# line_kick.net
KiCad netlist of a schematic drawn in EAGLE
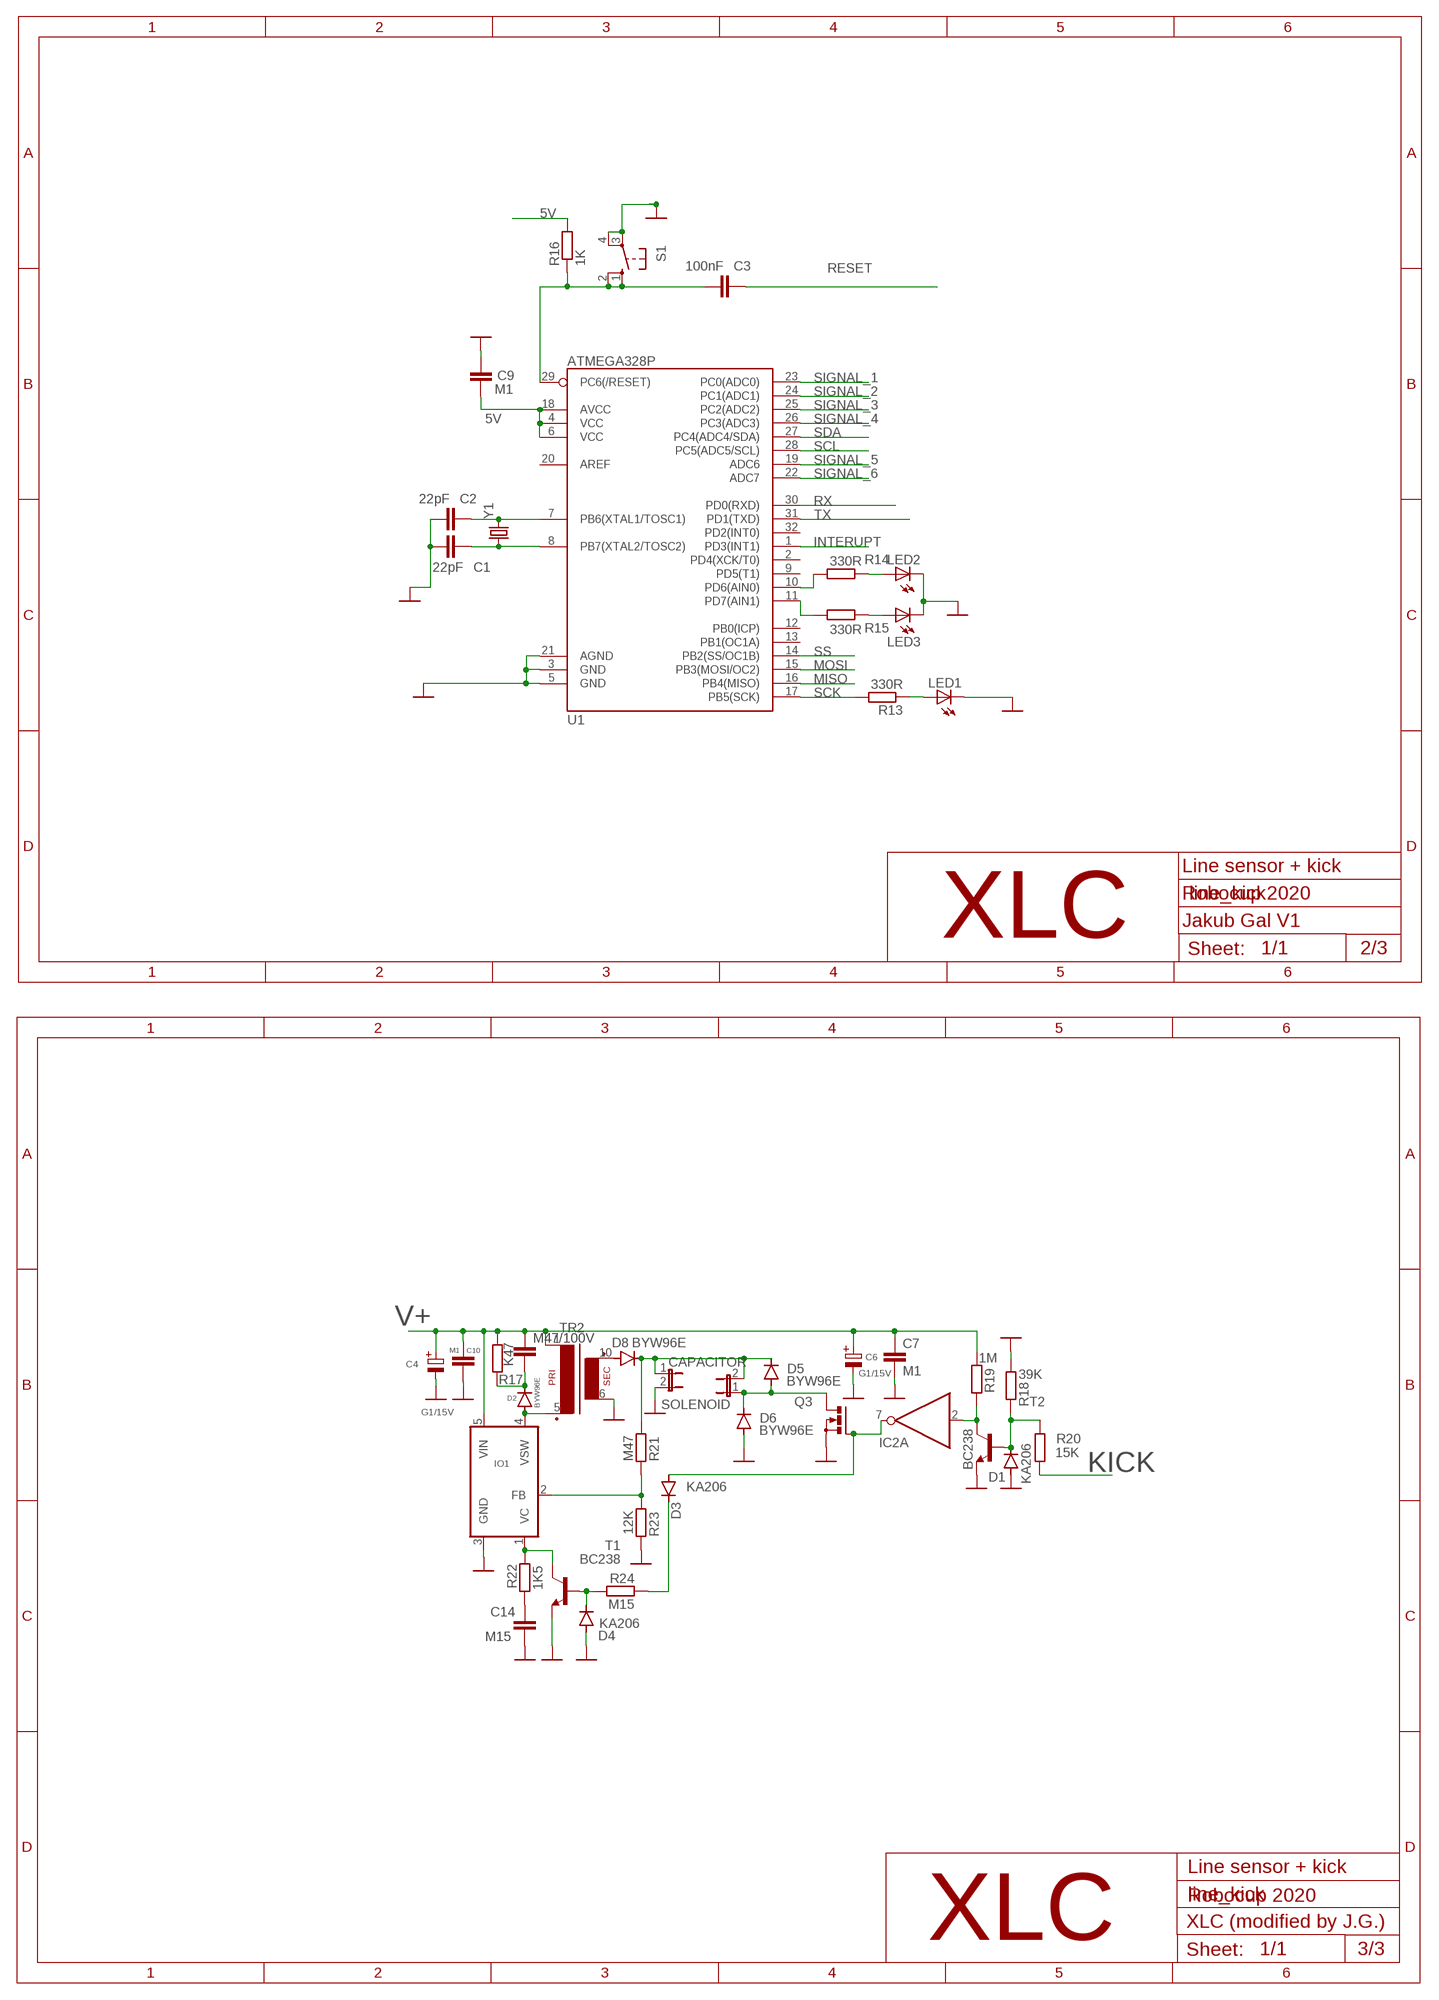
[diagram p0: schematic, sheet 1, part 1 of 2]
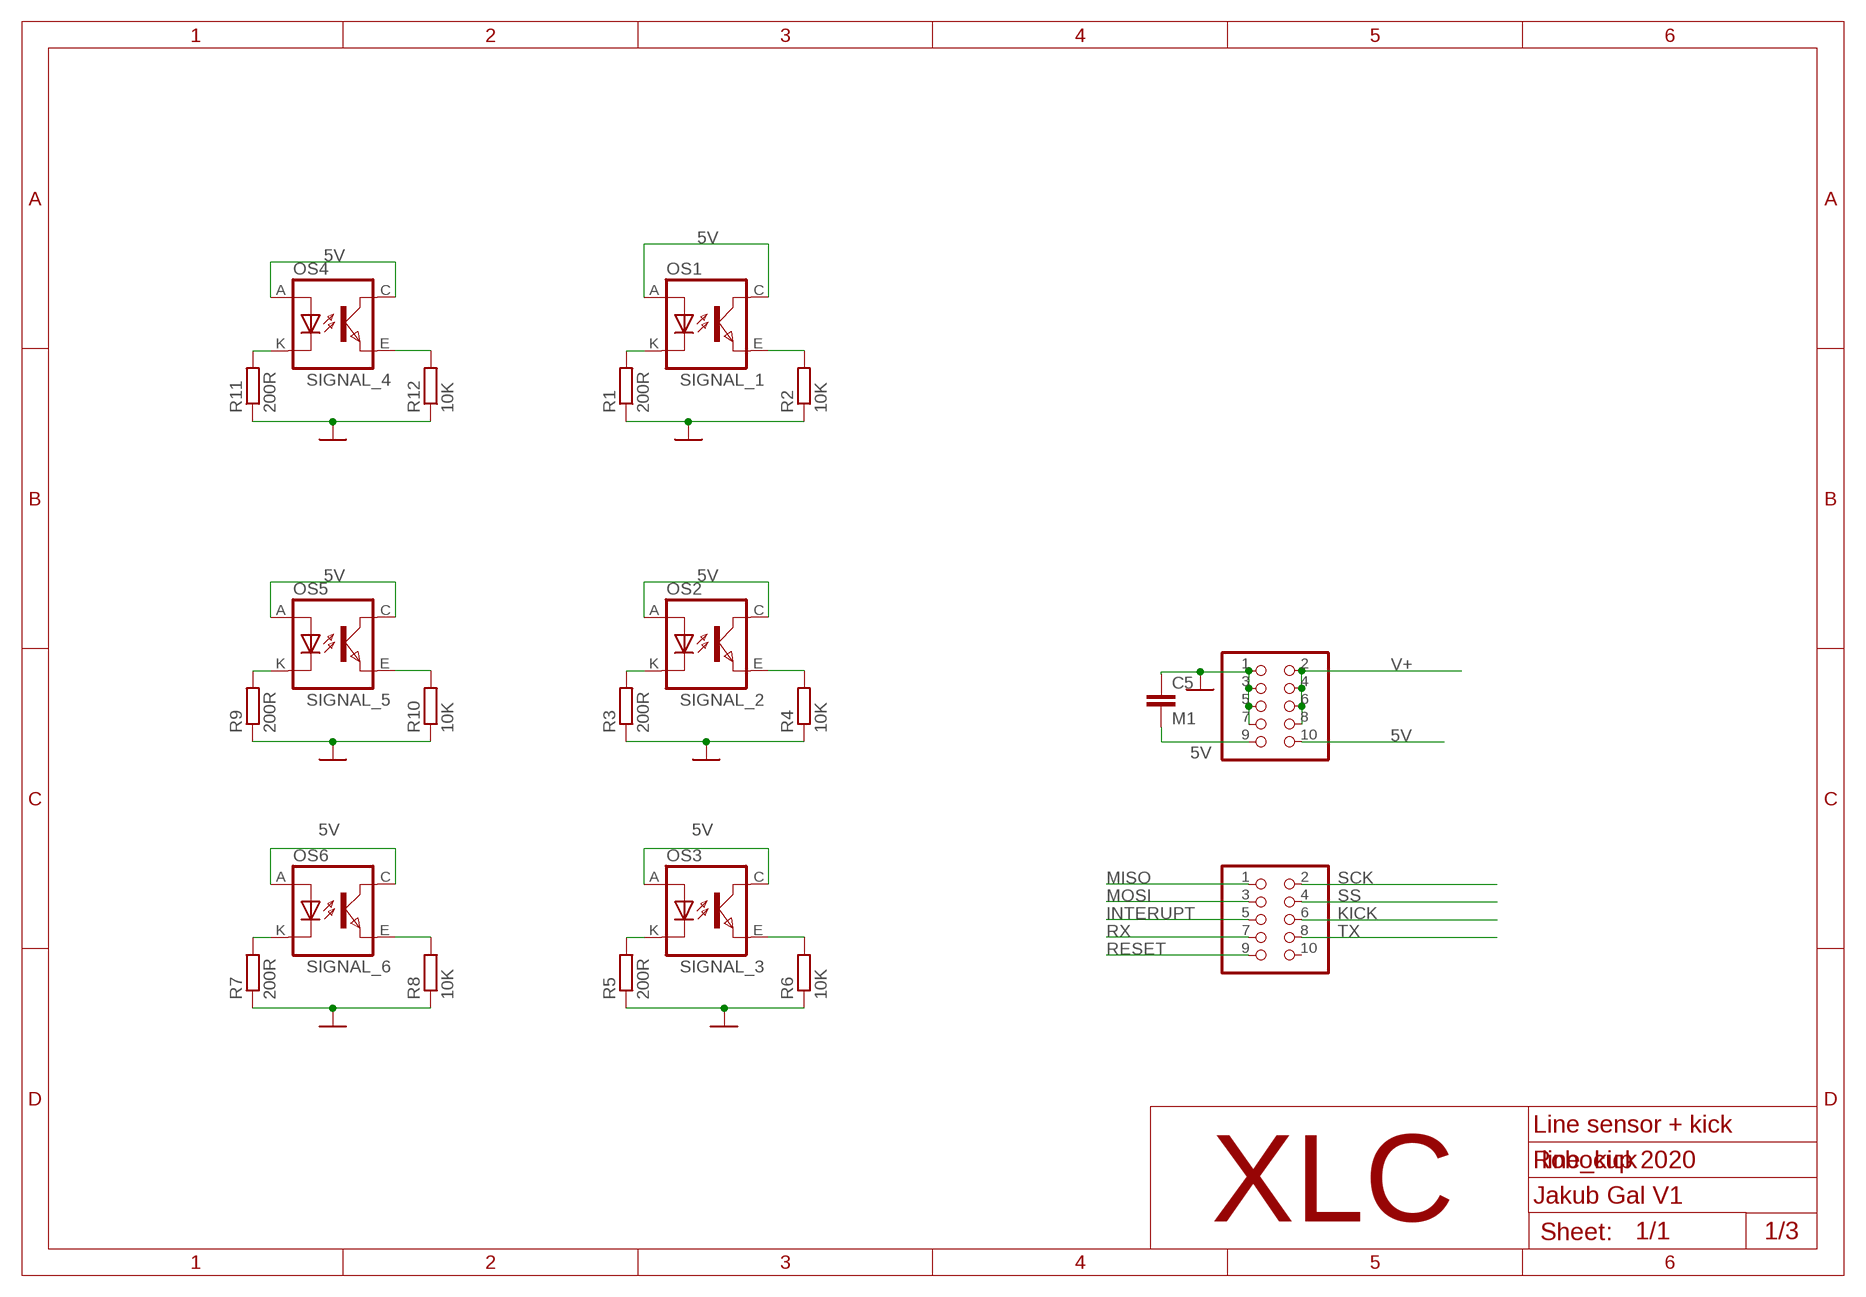
[diagram p1: schematic, sheet 1, part 2 of 2]

(export (version "E")
  (design (tool "Eeschema 10.0.6"))
  (components
    (comp (ref "C1")
      (value "22pF")
      (footprint "eagle-import:C0603")
      (libsource (lib "eagle-import") (part "C-EUC0603"))
    )
    (comp (ref "C2")
      (value "22pF")
      (footprint "eagle-import:C0603")
      (libsource (lib "eagle-import") (part "C-EUC0603"))
    )
    (comp (ref "C3")
      (value "100nF")
      (footprint "eagle-import:C0603")
      (libsource (lib "eagle-import") (part "C-EUC0603"))
    )
    (comp (ref "C4")
      (value "G1/15V")
      (footprint "eagle-import:E-2,5_7-RAD")
      (libsource (lib "eagle-import") (part "KOND-ELEKT-2,5/7"))
    )
    (comp (ref "C5")
      (value "M1")
      (footprint "eagle-import:C0603")
      (libsource (lib "eagle-import") (part "rcl_334_C-EUC0603"))
    )
    (comp (ref "C6")
      (value "G1/15V")
      (footprint "eagle-import:E-2,5_7-RAD")
      (libsource (lib "eagle-import") (part "KOND-ELEKT-2,5/7"))
    )
    (comp (ref "C7")
      (value "M1")
      (footprint "eagle-import:C0805K")
      (libsource (lib "eagle-import") (part "resistor_348_C-EUC0805K"))
    )
    (comp (ref "C9")
      (value "M1")
      (footprint "eagle-import:C0603")
      (libsource (lib "eagle-import") (part "C-EUC0603"))
    )
    (comp (ref "C10")
      (value "M1")
      (footprint "eagle-import:C0805K")
      (libsource (lib "eagle-import") (part "resistor_348_C-EUC0805K"))
    )
    (comp (ref "C14")
      (value "M15")
      (footprint "eagle-import:C0805K")
      (libsource (lib "eagle-import") (part "resistor_348_C-EUC0805K"))
    )
    (comp (ref "CAPACITOR")
      (value "JP1E")
      (footprint "eagle-import:JP1")
      (libsource (lib "eagle-import") (part "JP1E"))
    )
    (comp (ref "D1")
      (value "KA206")
      (footprint "eagle-import:D-7.5")
      (libsource (lib "eagle-import") (part "DIODE-D-7.5"))
    )
    (comp (ref "D2")
      (value "BYW96E")
      (footprint "eagle-import:SOD64-10")
      (libsource (lib "eagle-import") (part "BYW96"))
    )
    (comp (ref "D3")
      (value "KA206")
      (footprint "eagle-import:D-7.5")
      (libsource (lib "eagle-import") (part "DIODE-D-7.5"))
    )
    (comp (ref "D4")
      (value "KA206")
      (footprint "eagle-import:D-7.5")
      (libsource (lib "eagle-import") (part "DIODE-D-7.5"))
    )
    (comp (ref "D5")
      (value "BYW96E")
      (footprint "eagle-import:SOD64-10")
      (libsource (lib "eagle-import") (part "BYW96"))
    )
    (comp (ref "D6")
      (value "BYW96E")
      (footprint "eagle-import:SOD64-10")
      (libsource (lib "eagle-import") (part "BYW96"))
    )
    (comp (ref "D8")
      (value "BYW96E")
      (footprint "eagle-import:SOD64-10")
      (libsource (lib "eagle-import") (part "BYW96"))
    )
    (comp (ref "IC2")
      (value "MIC4423BM")
      (footprint "eagle-import:SO08")
      (libsource (lib "eagle-import") (part "MIC4423BM"))
    )
    (comp (ref "IO1")
      (value "LT1071V")
      (footprint "eagle-import:TO220-5P")
      (libsource (lib "eagle-import") (part "LT1071V"))
    )
    (comp (ref "JP2")
      (value "PINHD-2X5")
      (footprint "eagle-import:2X05")
      (libsource (lib "eagle-import") (part "PINHD-2X5"))
    )
    (comp (ref "JP3")
      (value "PINHD-2X5")
      (footprint "eagle-import:2X05")
      (libsource (lib "eagle-import") (part "PINHD-2X5"))
    )
    (comp (ref "LED1")
      (value "LEDCHIPLED_0603")
      (footprint "eagle-import:CHIPLED_0603")
      (libsource (lib "eagle-import") (part "LEDCHIPLED_0603"))
    )
    (comp (ref "LED2")
      (value "LEDCHIPLED_0603")
      (footprint "eagle-import:CHIPLED_0603")
      (libsource (lib "eagle-import") (part "LEDCHIPLED_0603"))
    )
    (comp (ref "LED3")
      (value "LEDCHIPLED_0603")
      (footprint "eagle-import:CHIPLED_0603")
      (libsource (lib "eagle-import") (part "LEDCHIPLED_0603"))
    )
    (comp (ref "M47/100V")
      (value "C-EUC0805K")
      (footprint "eagle-import:C0805K")
      (libsource (lib "eagle-import") (part "resistor_348_C-EUC0805K"))
    )
    (comp (ref "OS1")
      (value "TCRT5000")
      (footprint "eagle-import:TCRT5000")
      (libsource (lib "eagle-import") (part "TCRT5000"))
    )
    (comp (ref "OS2")
      (value "TCRT5000")
      (footprint "eagle-import:TCRT5000")
      (libsource (lib "eagle-import") (part "TCRT5000"))
    )
    (comp (ref "OS3")
      (value "TCRT5000")
      (footprint "eagle-import:TCRT5000")
      (libsource (lib "eagle-import") (part "TCRT5000"))
    )
    (comp (ref "OS4")
      (value "TCRT5000")
      (footprint "eagle-import:TCRT5000")
      (fields (field (name "SPICEPREFIX") "O"))
      (libsource (lib "eagle-import") (part "TCRT5000"))
    )
    (comp (ref "OS5")
      (value "TCRT5000")
      (footprint "eagle-import:TCRT5000")
      (libsource (lib "eagle-import") (part "TCRT5000"))
    )
    (comp (ref "OS6")
      (value "TCRT5000")
      (footprint "eagle-import:TCRT5000")
      (fields (field (name "SPICEPREFIX") "O"))
      (libsource (lib "eagle-import") (part "TCRT5000"))
    )
    (comp (ref "Q3")
      (value "PMOSFET_NTO220BV")
      (footprint "eagle-import:TO220BV")
      (libsource (lib "eagle-import") (part "PMOSFET_NTO220BV"))
    )
    (comp (ref "R1")
      (value "200R")
      (footprint "eagle-import:R0603")
      (libsource (lib "eagle-import") (part "R-EU_R0603"))
    )
    (comp (ref "R2")
      (value "10K")
      (footprint "eagle-import:R0603")
      (libsource (lib "eagle-import") (part "R-EU_R0603"))
    )
    (comp (ref "R3")
      (value "200R")
      (footprint "eagle-import:R0603")
      (libsource (lib "eagle-import") (part "R-EU_R0603"))
    )
    (comp (ref "R4")
      (value "10K")
      (footprint "eagle-import:R0603")
      (libsource (lib "eagle-import") (part "R-EU_R0603"))
    )
    (comp (ref "R5")
      (value "200R")
      (footprint "eagle-import:R0603")
      (libsource (lib "eagle-import") (part "R-EU_R0603"))
    )
    (comp (ref "R6")
      (value "10K")
      (footprint "eagle-import:R0603")
      (libsource (lib "eagle-import") (part "R-EU_R0603"))
    )
    (comp (ref "R7")
      (value "200R")
      (footprint "eagle-import:R0603")
      (libsource (lib "eagle-import") (part "R-EU_R0603"))
    )
    (comp (ref "R8")
      (value "10K")
      (footprint "eagle-import:R0603")
      (libsource (lib "eagle-import") (part "R-EU_R0603"))
    )
    (comp (ref "R9")
      (value "200R")
      (footprint "eagle-import:R0603")
      (libsource (lib "eagle-import") (part "R-EU_R0603"))
    )
    (comp (ref "R10")
      (value "10K")
      (footprint "eagle-import:R0603")
      (libsource (lib "eagle-import") (part "R-EU_R0603"))
    )
    (comp (ref "R11")
      (value "200R")
      (footprint "eagle-import:R0603")
      (libsource (lib "eagle-import") (part "R-EU_R0603"))
    )
    (comp (ref "R12")
      (value "10K")
      (footprint "eagle-import:R0603")
      (libsource (lib "eagle-import") (part "R-EU_R0603"))
    )
    (comp (ref "R13")
      (value "330R")
      (footprint "eagle-import:R0603")
      (libsource (lib "eagle-import") (part "R-EU_R0603"))
    )
    (comp (ref "R14")
      (value "330R")
      (footprint "eagle-import:R0603")
      (libsource (lib "eagle-import") (part "R-EU_R0603"))
    )
    (comp (ref "R15")
      (value "330R")
      (footprint "eagle-import:R0603")
      (libsource (lib "eagle-import") (part "R-EU_R0603"))
    )
    (comp (ref "R16")
      (value "1K")
      (footprint "eagle-import:R0603")
      (libsource (lib "eagle-import") (part "R-EU_R0603"))
    )
    (comp (ref "R17")
      (value "K47")
      (footprint "eagle-import:R0603")
      (libsource (lib "eagle-import") (part "resistor_348_R-EU_R0603"))
    )
    (comp (ref "R18")
      (value "39K")
      (footprint "eagle-import:R0603")
      (libsource (lib "eagle-import") (part "resistor_348_R-EU_R0603"))
    )
    (comp (ref "R19")
      (value "1M")
      (footprint "eagle-import:R0603")
      (libsource (lib "eagle-import") (part "resistor_348_R-EU_R0603"))
    )
    (comp (ref "R20")
      (value "15K")
      (footprint "eagle-import:R0603")
      (libsource (lib "eagle-import") (part "resistor_348_R-EU_R0603"))
    )
    (comp (ref "R21")
      (value "M47")
      (footprint "eagle-import:R0603")
      (libsource (lib "eagle-import") (part "resistor_348_R-EU_R0603"))
    )
    (comp (ref "R22")
      (value "1K5")
      (footprint "eagle-import:R0603")
      (libsource (lib "eagle-import") (part "resistor_348_R-EU_R0603"))
    )
    (comp (ref "R23")
      (value "12K")
      (footprint "eagle-import:R0603")
      (libsource (lib "eagle-import") (part "resistor_348_R-EU_R0603"))
    )
    (comp (ref "R24")
      (value "M15")
      (footprint "eagle-import:R0603")
      (libsource (lib "eagle-import") (part "resistor_348_R-EU_R0603"))
    )
    (comp (ref "S1")
      (value "10-XX")
      (footprint "eagle-import:B3F-10XX")
      (fields (field (name "MPN") "B3F-1000"))
      (libsource (lib "eagle-import") (part "10-XX"))
    )
    (comp (ref "SOLENOID")
      (value "JP1E")
      (footprint "eagle-import:JP1")
      (libsource (lib "eagle-import") (part "JP1E"))
    )
    (comp (ref "T1")
      (value "BC238")
      (footprint "eagle-import:TO92")
      (libsource (lib "eagle-import") (part "BC238"))
    )
    (comp (ref "T2")
      (value "BC238")
      (footprint "eagle-import:TO92")
      (libsource (lib "eagle-import") (part "BC238"))
    )
    (comp (ref "TR2")
      (value "TRAFO-E10-R\"\"")
      (footprint "eagle-import:TRAFO-EE17X20")
      (libsource (lib "eagle-import") (part "TRAFO-E10-R{dblquote}{dblquote}"))
    )
    (comp (ref "U1")
      (value "ATMEGA328P")
      (footprint "eagle-import:TQFP32-08")
      (libsource (lib "eagle-import") (part "ATMEGA328_SMT"))
    )
    (comp (ref "Y1")
      (value "CRYSTALHC49US")
      (footprint "eagle-import:HC49US")
      (libsource (lib "eagle-import") (part "CRYSTALHC49US"))
    )
  )
  (nets
    (net (code "1") (name "/5V") (class "Default")
      (node (ref "C5") (pin "2") (pinfunction "2_2") (pintype "passive"))
      (node (ref "C9") (pin "1") (pinfunction "1_1") (pintype "passive"))
      (node (ref "JP3") (pin "10") (pinfunction "10_10") (pintype "passive"))
      (node (ref "JP3") (pin "9") (pinfunction "9_9") (pintype "passive"))
      (node (ref "OS1") (pin "A") (pinfunction "ANODE_A") (pintype "passive"))
      (node (ref "OS1") (pin "C") (pinfunction "COLLECTOR_C") (pintype "passive"))
      (node (ref "OS2") (pin "A") (pinfunction "ANODE_A") (pintype "passive"))
      (node (ref "OS2") (pin "C") (pinfunction "COLLECTOR_C") (pintype "passive"))
      (node (ref "OS3") (pin "A") (pinfunction "ANODE_A") (pintype "passive"))
      (node (ref "OS3") (pin "C") (pinfunction "COLLECTOR_C") (pintype "passive"))
      (node (ref "OS4") (pin "A") (pinfunction "ANODE_A") (pintype "passive"))
      (node (ref "OS4") (pin "C") (pinfunction "COLLECTOR_C") (pintype "passive"))
      (node (ref "OS5") (pin "A") (pinfunction "ANODE_A") (pintype "passive"))
      (node (ref "OS5") (pin "C") (pinfunction "COLLECTOR_C") (pintype "passive"))
      (node (ref "OS6") (pin "A") (pinfunction "ANODE_A") (pintype "passive"))
      (node (ref "OS6") (pin "C") (pinfunction "COLLECTOR_C") (pintype "passive"))
      (node (ref "R16") (pin "2") (pinfunction "2_2") (pintype "passive"))
      (node (ref "U1") (pin "18") (pinfunction "AVCC_18") (pintype "bidirectional"))
      (node (ref "U1") (pin "4") (pinfunction "VCC_4") (pintype "bidirectional"))
      (node (ref "U1") (pin "6") (pinfunction "VCC_6") (pintype "bidirectional"))
    )
    (net (code "2") (name "/INTERUPT") (class "Default")
      (node (ref "JP2") (pin "5") (pinfunction "5_5") (pintype "passive"))
      (node (ref "U1") (pin "1") (pinfunction "PD3(INT1)_1") (pintype "bidirectional"))
    )
    (net (code "3") (name "/KICK") (class "Default")
      (node (ref "JP2") (pin "6") (pinfunction "6_6") (pintype "passive"))
      (node (ref "R20") (pin "1") (pinfunction "1_1") (pintype "passive"))
    )
    (net (code "4") (name "/MISO") (class "Default")
      (node (ref "JP2") (pin "1") (pinfunction "1_1") (pintype "passive"))
      (node (ref "U1") (pin "16") (pinfunction "PB4(MISO)_16") (pintype "bidirectional"))
    )
    (net (code "5") (name "/MOSI") (class "Default")
      (node (ref "JP2") (pin "3") (pinfunction "3_3") (pintype "passive"))
      (node (ref "U1") (pin "15") (pinfunction "PB3(MOSI/OC2)_15") (pintype "bidirectional"))
    )
    (net (code "6") (name "/RESET") (class "Default")
      (node (ref "C3") (pin "2") (pinfunction "2_2") (pintype "passive"))
      (node (ref "JP2") (pin "9") (pinfunction "9_9") (pintype "passive"))
    )
    (net (code "7") (name "/RX") (class "Default")
      (node (ref "JP2") (pin "7") (pinfunction "7_7") (pintype "passive"))
      (node (ref "U1") (pin "30") (pinfunction "PD0(RXD)_30") (pintype "bidirectional"))
    )
    (net (code "8") (name "/SCK") (class "Default")
      (node (ref "JP2") (pin "2") (pinfunction "2_2") (pintype "passive"))
      (node (ref "R13") (pin "2") (pinfunction "2_2") (pintype "passive"))
      (node (ref "U1") (pin "17") (pinfunction "PB5(SCK)_17") (pintype "bidirectional"))
    )
    (net (code "9") (name "/SCL") (class "Default")
      (node (ref "U1") (pin "28") (pinfunction "PC5(ADC5/SCL)_28") (pintype "bidirectional"))
    )
    (net (code "10") (name "/SDA") (class "Default")
      (node (ref "U1") (pin "27") (pinfunction "PC4(ADC4/SDA)_27") (pintype "bidirectional"))
    )
    (net (code "11") (name "/SIGNAL_1") (class "Default")
      (node (ref "OS1") (pin "E") (pinfunction "EMITTER_E") (pintype "passive"))
      (node (ref "R2") (pin "2") (pinfunction "2_2") (pintype "passive"))
      (node (ref "U1") (pin "23") (pinfunction "PC0(ADC0)_23") (pintype "bidirectional"))
    )
    (net (code "12") (name "/SIGNAL_2") (class "Default")
      (node (ref "OS2") (pin "E") (pinfunction "EMITTER_E") (pintype "passive"))
      (node (ref "R4") (pin "2") (pinfunction "2_2") (pintype "passive"))
      (node (ref "U1") (pin "24") (pinfunction "PC1(ADC1)_24") (pintype "bidirectional"))
    )
    (net (code "13") (name "/SIGNAL_3") (class "Default")
      (node (ref "OS3") (pin "E") (pinfunction "EMITTER_E") (pintype "passive"))
      (node (ref "R6") (pin "2") (pinfunction "2_2") (pintype "passive"))
      (node (ref "U1") (pin "25") (pinfunction "PC2(ADC2)_25") (pintype "bidirectional"))
    )
    (net (code "14") (name "/SIGNAL_4") (class "Default")
      (node (ref "OS4") (pin "E") (pinfunction "EMITTER_E") (pintype "passive"))
      (node (ref "R12") (pin "2") (pinfunction "2_2") (pintype "passive"))
      (node (ref "U1") (pin "26") (pinfunction "PC3(ADC3)_26") (pintype "bidirectional"))
    )
    (net (code "15") (name "/SIGNAL_5") (class "Default")
      (node (ref "OS5") (pin "E") (pinfunction "EMITTER_E") (pintype "passive"))
      (node (ref "R10") (pin "2") (pinfunction "2_2") (pintype "passive"))
      (node (ref "U1") (pin "19") (pinfunction "ADC6_19") (pintype "bidirectional"))
    )
    (net (code "16") (name "/SIGNAL_6") (class "Default")
      (node (ref "OS6") (pin "E") (pinfunction "EMITTER_E") (pintype "passive"))
      (node (ref "R8") (pin "2") (pinfunction "2_2") (pintype "passive"))
      (node (ref "U1") (pin "22") (pinfunction "ADC7_22") (pintype "bidirectional"))
    )
    (net (code "17") (name "/SS") (class "Default")
      (node (ref "JP2") (pin "4") (pinfunction "4_4") (pintype "passive"))
      (node (ref "U1") (pin "14") (pinfunction "PB2(SS/OC1B)_14") (pintype "bidirectional"))
    )
    (net (code "18") (name "/TX") (class "Default")
      (node (ref "JP2") (pin "8") (pinfunction "8_8") (pintype "passive"))
      (node (ref "U1") (pin "31") (pinfunction "PD1(TXD)_31") (pintype "bidirectional"))
    )
    (net (code "19") (name "/V+") (class "Default")
      (node (ref "C10") (pin "1") (pinfunction "1_1") (pintype "passive"))
      (node (ref "C4") (pin "+") (pinfunction "+_+") (pintype "passive"))
      (node (ref "C6") (pin "+") (pinfunction "+_+") (pintype "passive"))
      (node (ref "C7") (pin "1") (pinfunction "1_1") (pintype "passive"))
      (node (ref "IO1") (pin "5") (pinfunction "VIN_5") (pintype "power_in"))
      (node (ref "JP3") (pin "2") (pinfunction "2_2") (pintype "passive"))
      (node (ref "JP3") (pin "4") (pinfunction "4_4") (pintype "passive"))
      (node (ref "JP3") (pin "6") (pinfunction "6_6") (pintype "passive"))
      (node (ref "JP3") (pin "8") (pinfunction "8_8") (pintype "passive"))
      (node (ref "M47/100V") (pin "1") (pinfunction "1_1") (pintype "passive"))
      (node (ref "R17") (pin "1") (pinfunction "1_1") (pintype "passive"))
      (node (ref "R19") (pin "2") (pinfunction "2_2") (pintype "passive"))
      (node (ref "TR2") (pin "1") (pinfunction "1_1") (pintype "passive"))
    )
    (net (code "20") (name "GND") (class "Default")
      (node (ref "C1") (pin "1") (pinfunction "1_1") (pintype "passive"))
      (node (ref "C10") (pin "2") (pinfunction "2_2") (pintype "passive"))
      (node (ref "C14") (pin "2") (pinfunction "2_2") (pintype "passive"))
      (node (ref "C2") (pin "1") (pinfunction "1_1") (pintype "passive"))
      (node (ref "C4") (pin "-") (pinfunction "-_-") (pintype "passive"))
      (node (ref "C5") (pin "1") (pinfunction "1_1") (pintype "passive"))
      (node (ref "C6") (pin "-") (pinfunction "-_-") (pintype "passive"))
      (node (ref "C7") (pin "2") (pinfunction "2_2") (pintype "passive"))
      (node (ref "C9") (pin "2") (pinfunction "2_2") (pintype "passive"))
      (node (ref "CAPACITOR") (pin "2") (pinfunction "2_2") (pintype "passive"))
      (node (ref "D1") (pin "A") (pinfunction "A_A") (pintype "passive"))
      (node (ref "D4") (pin "A") (pinfunction "A_A") (pintype "passive"))
      (node (ref "D6") (pin "A") (pinfunction "A_A") (pintype "passive"))
      (node (ref "IO1") (pin "3") (pinfunction "GND_3") (pintype "power_in"))
      (node (ref "JP3") (pin "1") (pinfunction "1_1") (pintype "passive"))
      (node (ref "JP3") (pin "3") (pinfunction "3_3") (pintype "passive"))
      (node (ref "JP3") (pin "5") (pinfunction "5_5") (pintype "passive"))
      (node (ref "JP3") (pin "7") (pinfunction "7_7") (pintype "passive"))
      (node (ref "LED1") (pin "C") (pinfunction "C_C") (pintype "passive"))
      (node (ref "LED2") (pin "C") (pinfunction "C_C") (pintype "passive"))
      (node (ref "LED3") (pin "C") (pinfunction "C_C") (pintype "passive"))
      (node (ref "Q3") (pin "S") (pinfunction "S_S") (pintype "passive"))
      (node (ref "R1") (pin "1") (pinfunction "1_1") (pintype "passive"))
      (node (ref "R10") (pin "1") (pinfunction "1_1") (pintype "passive"))
      (node (ref "R11") (pin "1") (pinfunction "1_1") (pintype "passive"))
      (node (ref "R12") (pin "1") (pinfunction "1_1") (pintype "passive"))
      (node (ref "R18") (pin "2") (pinfunction "2_2") (pintype "passive"))
      (node (ref "R2") (pin "1") (pinfunction "1_1") (pintype "passive"))
      (node (ref "R23") (pin "1") (pinfunction "1_1") (pintype "passive"))
      (node (ref "R3") (pin "1") (pinfunction "1_1") (pintype "passive"))
      (node (ref "R4") (pin "1") (pinfunction "1_1") (pintype "passive"))
      (node (ref "R5") (pin "1") (pinfunction "1_1") (pintype "passive"))
      (node (ref "R6") (pin "1") (pinfunction "1_1") (pintype "passive"))
      (node (ref "R7") (pin "1") (pinfunction "1_1") (pintype "passive"))
      (node (ref "R8") (pin "1") (pinfunction "1_1") (pintype "passive"))
      (node (ref "R9") (pin "1") (pinfunction "1_1") (pintype "passive"))
      (node (ref "S1") (pin "3") (pinfunction "P_3") (pintype "passive"))
      (node (ref "S1") (pin "4") (pinfunction "P1_4") (pintype "passive"))
      (node (ref "T1") (pin "1") (pinfunction "E_1") (pintype "passive"))
      (node (ref "T2") (pin "1") (pinfunction "E_1") (pintype "passive"))
      (node (ref "TR2") (pin "6") (pinfunction "3_6") (pintype "passive"))
      (node (ref "U1") (pin "21") (pinfunction "AGND_21") (pintype "bidirectional"))
      (node (ref "U1") (pin "3") (pinfunction "GND_3") (pintype "bidirectional"))
      (node (ref "U1") (pin "5") (pinfunction "GND_5") (pintype "bidirectional"))
    )
    (net (code "21") (name "Net-(C14-Pad1)") (class "Default")
      (node (ref "C14") (pin "1") (pinfunction "1_1") (pintype "passive"))
      (node (ref "R22") (pin "2") (pinfunction "2_2") (pintype "passive"))
    )
    (net (code "22") (name "Net-(CAPACITOR-Pad1)") (class "Default")
      (node (ref "CAPACITOR") (pin "1") (pinfunction "1_1") (pintype "passive"))
      (node (ref "D5") (pin "C") (pinfunction "C_C") (pintype "passive"))
      (node (ref "D8") (pin "C") (pinfunction "C_C") (pintype "passive"))
      (node (ref "R21") (pin "2") (pinfunction "2_2") (pintype "passive"))
      (node (ref "SOLENOID") (pin "2") (pinfunction "2_2") (pintype "passive"))
    )
    (net (code "23") (name "Net-(D2-PadC)") (class "Default")
      (node (ref "D2") (pin "C") (pinfunction "C_C") (pintype "passive"))
      (node (ref "M47/100V") (pin "2") (pinfunction "2_2") (pintype "passive"))
      (node (ref "R17") (pin "2") (pinfunction "2_2") (pintype "passive"))
    )
    (net (code "24") (name "Net-(D3-PadC)") (class "Default")
      (node (ref "D3") (pin "C") (pinfunction "C_C") (pintype "passive"))
      (node (ref "R24") (pin "1") (pinfunction "1_1") (pintype "passive"))
    )
    (net (code "25") (name "Net-(D5-PadA)") (class "Default")
      (node (ref "D5") (pin "A") (pinfunction "A_A") (pintype "passive"))
      (node (ref "D6") (pin "C") (pinfunction "C_C") (pintype "passive"))
      (node (ref "Q3") (pin "D") (pinfunction "D_D") (pintype "passive"))
      (node (ref "SOLENOID") (pin "1") (pinfunction "1_1") (pintype "passive"))
    )
    (net (code "26") (name "Net-(IC2A-IN)") (class "Default")
      (node (ref "IC2") (pin "2") (pinfunction "IN_2") (pintype "input"))
      (node (ref "R19") (pin "1") (pinfunction "1_1") (pintype "passive"))
      (node (ref "T2") (pin "3") (pinfunction "C_3") (pintype "passive"))
    )
    (net (code "27") (name "Net-(IC2A-OUT)") (class "Default")
      (node (ref "D3") (pin "A") (pinfunction "A_A") (pintype "passive"))
      (node (ref "IC2") (pin "7") (pinfunction "OUT_7") (pintype "output"))
      (node (ref "Q3") (pin "G") (pinfunction "G_G") (pintype "passive"))
    )
    (net (code "28") (name "Net-(IO1-FB)") (class "Default")
      (node (ref "IO1") (pin "2") (pinfunction "FB_2") (pintype "input"))
      (node (ref "R21") (pin "1") (pinfunction "1_1") (pintype "passive"))
      (node (ref "R23") (pin "2") (pinfunction "2_2") (pintype "passive"))
    )
    (net (code "29") (name "Net-(IO1-VC)") (class "Default")
      (node (ref "IO1") (pin "1") (pinfunction "VC_1") (pintype "input"))
      (node (ref "R22") (pin "1") (pinfunction "1_1") (pintype "passive"))
      (node (ref "T1") (pin "3") (pinfunction "C_3") (pintype "passive"))
    )
    (net (code "30") (name "Net-(IO1-VSW)") (class "Default")
      (node (ref "D2") (pin "A") (pinfunction "A_A") (pintype "passive"))
      (node (ref "IO1") (pin "4") (pinfunction "VSW_4") (pintype "output"))
      (node (ref "TR2") (pin "5") (pinfunction "2_5") (pintype "passive"))
    )
    (net (code "31") (name "Net-(LED1-PadA)") (class "Default")
      (node (ref "LED1") (pin "A") (pinfunction "A_A") (pintype "passive"))
      (node (ref "R13") (pin "1") (pinfunction "1_1") (pintype "passive"))
    )
    (net (code "32") (name "Net-(LED2-PadA)") (class "Default")
      (node (ref "LED2") (pin "A") (pinfunction "A_A") (pintype "passive"))
      (node (ref "R14") (pin "1") (pinfunction "1_1") (pintype "passive"))
    )
    (net (code "33") (name "Net-(LED3-PadA)") (class "Default")
      (node (ref "LED3") (pin "A") (pinfunction "A_A") (pintype "passive"))
      (node (ref "R15") (pin "1") (pinfunction "1_1") (pintype "passive"))
    )
    (net (code "34") (name "Net-(OS1-CATHODE)") (class "Default")
      (node (ref "OS1") (pin "K") (pinfunction "CATHODE_K") (pintype "passive"))
      (node (ref "R1") (pin "2") (pinfunction "2_2") (pintype "passive"))
    )
    (net (code "35") (name "Net-(OS2-CATHODE)") (class "Default")
      (node (ref "OS2") (pin "K") (pinfunction "CATHODE_K") (pintype "passive"))
      (node (ref "R3") (pin "2") (pinfunction "2_2") (pintype "passive"))
    )
    (net (code "36") (name "Net-(OS3-CATHODE)") (class "Default")
      (node (ref "OS3") (pin "K") (pinfunction "CATHODE_K") (pintype "passive"))
      (node (ref "R5") (pin "2") (pinfunction "2_2") (pintype "passive"))
    )
    (net (code "37") (name "Net-(OS4-CATHODE)") (class "Default")
      (node (ref "OS4") (pin "K") (pinfunction "CATHODE_K") (pintype "passive"))
      (node (ref "R11") (pin "2") (pinfunction "2_2") (pintype "passive"))
    )
    (net (code "38") (name "Net-(OS5-CATHODE)") (class "Default")
      (node (ref "OS5") (pin "K") (pinfunction "CATHODE_K") (pintype "passive"))
      (node (ref "R9") (pin "2") (pinfunction "2_2") (pintype "passive"))
    )
    (net (code "39") (name "Net-(OS6-CATHODE)") (class "Default")
      (node (ref "OS6") (pin "K") (pinfunction "CATHODE_K") (pintype "passive"))
      (node (ref "R7") (pin "2") (pinfunction "2_2") (pintype "passive"))
    )
    (net (code "40") (name "Net-(S1-S)") (class "Default")
      (node (ref "C3") (pin "1") (pinfunction "1_1") (pintype "passive"))
      (node (ref "R16") (pin "1") (pinfunction "1_1") (pintype "passive"))
      (node (ref "S1") (pin "1") (pinfunction "S_1") (pintype "passive"))
      (node (ref "S1") (pin "2") (pinfunction "S1_2") (pintype "passive"))
      (node (ref "U1") (pin "29") (pinfunction "PC6(/RESET)_29") (pintype "bidirectional"))
    )
    (net (code "41") (name "Net-(T1-B)") (class "Default")
      (node (ref "D4") (pin "C") (pinfunction "C_C") (pintype "passive"))
      (node (ref "R24") (pin "2") (pinfunction "2_2") (pintype "passive"))
      (node (ref "T1") (pin "2") (pinfunction "B_2") (pintype "passive"))
    )
    (net (code "42") (name "Net-(T2-B)") (class "Default")
      (node (ref "D1") (pin "C") (pinfunction "C_C") (pintype "passive"))
      (node (ref "R18") (pin "1") (pinfunction "1_1") (pintype "passive"))
      (node (ref "R20") (pin "2") (pinfunction "2_2") (pintype "passive"))
      (node (ref "T2") (pin "2") (pinfunction "B_2") (pintype "passive"))
    )
    (net (code "43") (name "Net-(TR2-4)") (class "Default")
      (node (ref "D8") (pin "A") (pinfunction "A_A") (pintype "passive"))
      (node (ref "TR2") (pin "10") (pinfunction "4_10") (pintype "passive"))
    )
    (net (code "44") (name "Net-(U1-PB6(XTAL1{slash}TOSC1))") (class "Default")
      (node (ref "C2") (pin "2") (pinfunction "2_2") (pintype "passive"))
      (node (ref "U1") (pin "7") (pinfunction "PB6(XTAL1/TOSC1)_7") (pintype "bidirectional"))
      (node (ref "Y1") (pin "2") (pinfunction "2_2") (pintype "passive"))
    )
    (net (code "45") (name "Net-(U1-PB7(XTAL2{slash}TOSC2))") (class "Default")
      (node (ref "C1") (pin "2") (pinfunction "2_2") (pintype "passive"))
      (node (ref "U1") (pin "8") (pinfunction "PB7(XTAL2/TOSC2)_8") (pintype "bidirectional"))
      (node (ref "Y1") (pin "1") (pinfunction "1_1") (pintype "passive"))
    )
    (net (code "46") (name "Net-(U1-PD6(AIN0))") (class "Default")
      (node (ref "R14") (pin "2") (pinfunction "2_2") (pintype "passive"))
      (node (ref "U1") (pin "10") (pinfunction "PD6(AIN0)_10") (pintype "bidirectional"))
    )
    (net (code "47") (name "Net-(U1-PD7(AIN1))") (class "Default")
      (node (ref "R15") (pin "2") (pinfunction "2_2") (pintype "passive"))
      (node (ref "U1") (pin "11") (pinfunction "PD7(AIN1)_11") (pintype "bidirectional"))
    )
    (net (code "48") (name "unconnected-(JP2-Pad10)") (class "Default")
      (node (ref "JP2") (pin "10") (pinfunction "10_10") (pintype "passive"))
    )
    (net (code "49") (name "unconnected-(U1-AREF-Pad20)") (class "Default")
      (node (ref "U1") (pin "20") (pinfunction "AREF_20") (pintype "bidirectional"))
    )
    (net (code "50") (name "unconnected-(U1-PB0(ICP)-Pad12)") (class "Default")
      (node (ref "U1") (pin "12") (pinfunction "PB0(ICP)_12") (pintype "bidirectional"))
    )
    (net (code "51") (name "unconnected-(U1-PB1(OC1A)-Pad13)") (class "Default")
      (node (ref "U1") (pin "13") (pinfunction "PB1(OC1A)_13") (pintype "bidirectional"))
    )
    (net (code "52") (name "unconnected-(U1-PD2(INT0)-Pad32)") (class "Default")
      (node (ref "U1") (pin "32") (pinfunction "PD2(INT0)_32") (pintype "bidirectional"))
    )
    (net (code "53") (name "unconnected-(U1-PD4(XCK{slash}T0)-Pad2)") (class "Default")
      (node (ref "U1") (pin "2") (pinfunction "PD4(XCK/T0)_2") (pintype "bidirectional"))
    )
    (net (code "54") (name "unconnected-(U1-PD5(T1)-Pad9)") (class "Default")
      (node (ref "U1") (pin "9") (pinfunction "PD5(T1)_9") (pintype "bidirectional"))
    )
  )
)
